# I2C_Multiplexer.net
KiCad netlist of a schematic drawn in Altium Designer
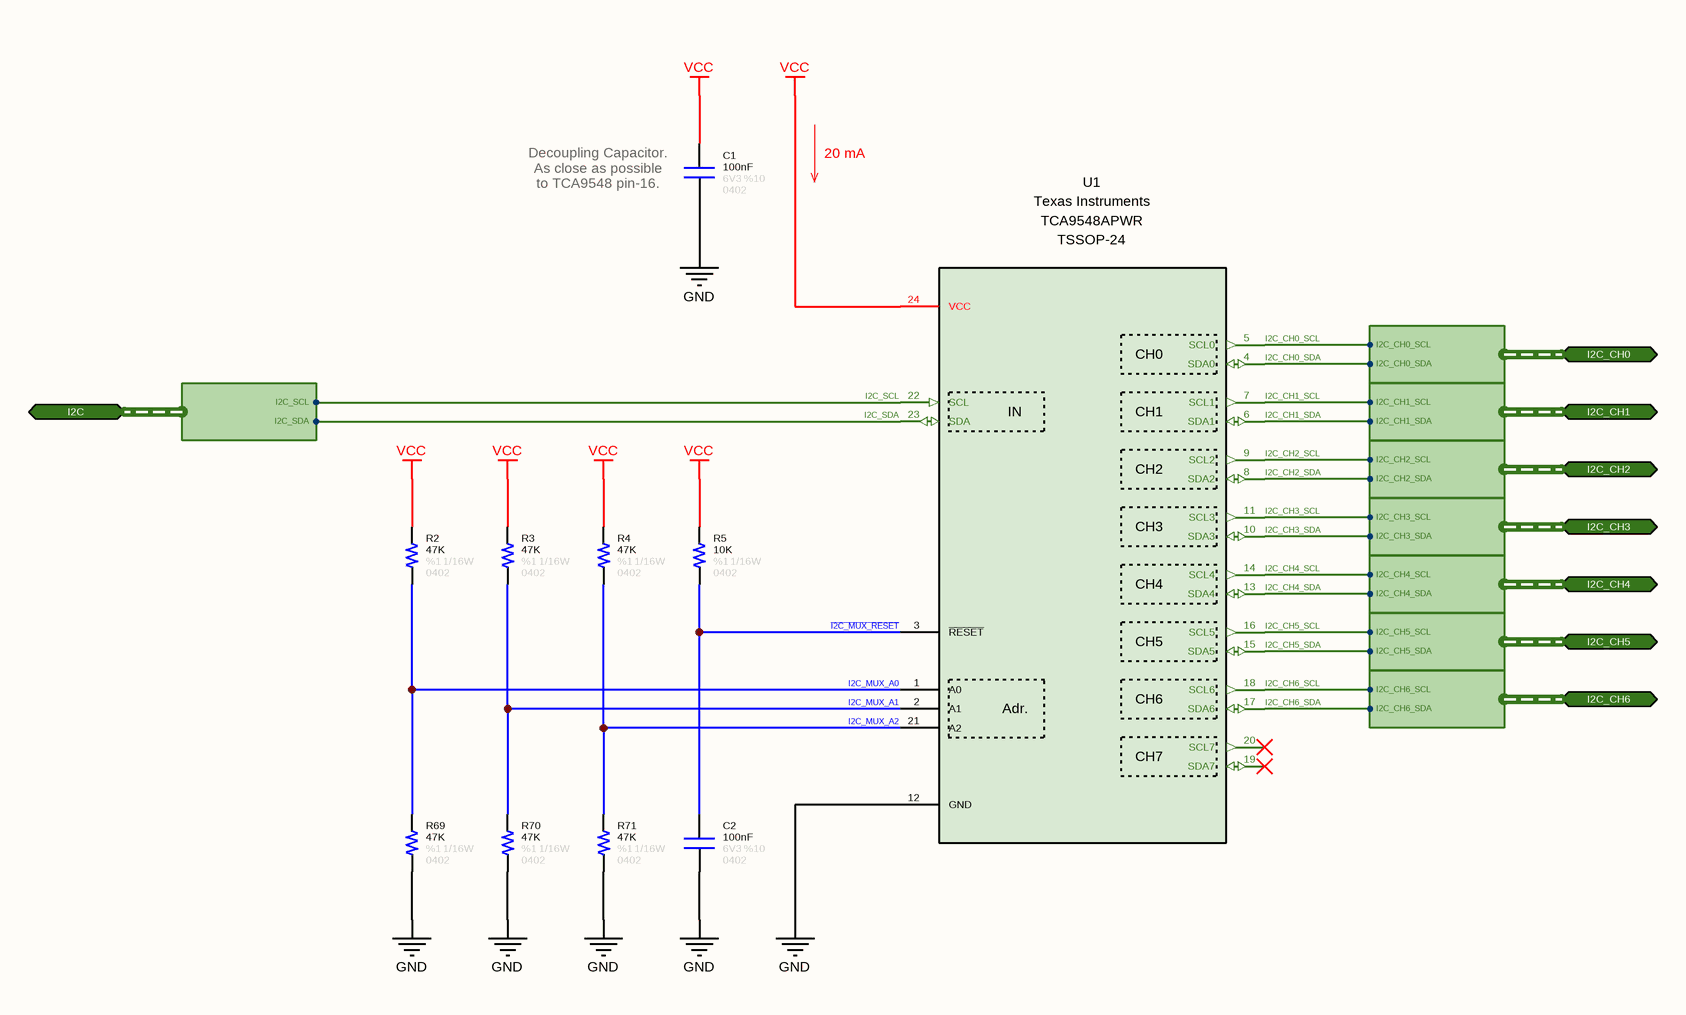
[diagram p0: I2C Multiplexer.SchDoc]

(export (version "E")
  (design (tool "Eeschema 10.0.6"))
  (components
    (comp (ref "C1")
      (value "100nF")
      (footprint "CAPACITOR_0402")
      (description "Capacitor - 100nF [0402-6V3] (Ceramic)")
      (fields
        (field (name "MANUFACTURER PART NUMBER") "04026D104KAT4A")
        (field (name "TOLERANCE") "%10")
        (field (name "VOLTAGE") "6V3")
        (field (name "CASE") "0402")
        (field (name "Comment") "Capacitor - 100nF [0402] (Ceramic)")
      )
      (libsource (lib "P101DA_Library") (part "Capacitor - 100nF [0402-6V3]"))
    )
    (comp (ref "C2")
      (value "100nF")
      (footprint "CAPACITOR_0402")
      (description "Capacitor - 100nF [0402-6V3] (Ceramic)")
      (fields
        (field (name "MANUFACTURER PART NUMBER") "04026D104KAT4A")
        (field (name "TOLERANCE") "%10")
        (field (name "VOLTAGE") "6V3")
        (field (name "CASE") "0402")
        (field (name "Comment") "Capacitor - 100nF [0402] (Ceramic)")
      )
      (libsource (lib "P101DA_Library") (part "Capacitor - 100nF [0402-6V3]"))
    )
    (comp (ref "R2")
      (value "47K")
      (footprint "RESISTOR_0402")
      (description "Thick Film Resistors - SMD 1/16 W 47 KOhm 1%")
      (fields
        (field (name "MANUFACTURER PART NUMBER") "CRCW040247K0FKED")
        (field (name "TOLERANCE") "%1")
        (field (name "CASE") "0402")
        (field (name "POWER") "1/16W")
        (field (name "Comment") "47K - 0402 - %1 - 1/16W")
      )
      (libsource (lib "P101DA_Library") (part "Resistor - 47K [0402]"))
    )
    (comp (ref "R3")
      (value "47K")
      (footprint "RESISTOR_0402")
      (description "Thick Film Resistors - SMD 1/16 W 47 KOhm 1%")
      (fields
        (field (name "MANUFACTURER PART NUMBER") "CRCW040247K0FKED")
        (field (name "TOLERANCE") "%1")
        (field (name "CASE") "0402")
        (field (name "POWER") "1/16W")
        (field (name "Comment") "47K - 0402 - %1 - 1/16W")
      )
      (libsource (lib "P101DA_Library") (part "Resistor - 47K [0402]"))
    )
    (comp (ref "R4")
      (value "47K")
      (footprint "RESISTOR_0402")
      (description "Thick Film Resistors - SMD 1/16 W 47 KOhm 1%")
      (fields
        (field (name "MANUFACTURER PART NUMBER") "CRCW040247K0FKED")
        (field (name "TOLERANCE") "%1")
        (field (name "CASE") "0402")
        (field (name "POWER") "1/16W")
        (field (name "Comment") "47K - 0402 - %1 - 1/16W")
      )
      (libsource (lib "P101DA_Library") (part "Resistor - 47K [0402]"))
    )
    (comp (ref "R5")
      (value "10K")
      (footprint "RESISTOR_0402")
      (description "Thick Film Resistors - SMD 1/16 W 10 KOhm 1%")
      (fields
        (field (name "MANUFACTURER PART NUMBER") "CRCW040210K0FKED")
        (field (name "TOLERANCE") "%1")
        (field (name "CASE") "0402")
        (field (name "POWER") "1/16W")
        (field (name "Comment") "10K - 0402 - %1 - 1/16W")
      )
      (libsource (lib "P101DA_Library") (part "Resistor - 10K [0402]"))
    )
    (comp (ref "R69")
      (value "47K")
      (footprint "RESISTOR_0402")
      (description "Thick Film Resistors - SMD 1/16 W 47 KOhm 1%")
      (fields
        (field (name "MANUFACTURER PART NUMBER") "CRCW040247K0FKED")
        (field (name "TOLERANCE") "%1")
        (field (name "CASE") "0402")
        (field (name "POWER") "1/16W")
        (field (name "Comment") "47K - 0402 - %1 - 1/16W")
      )
      (libsource (lib "P101DA_Library") (part "Resistor - 47K [0402]"))
    )
    (comp (ref "R70")
      (value "47K")
      (footprint "RESISTOR_0402")
      (description "Thick Film Resistors - SMD 1/16 W 47 KOhm 1%")
      (fields
        (field (name "MANUFACTURER PART NUMBER") "CRCW040247K0FKED")
        (field (name "TOLERANCE") "%1")
        (field (name "CASE") "0402")
        (field (name "POWER") "1/16W")
        (field (name "Comment") "47K - 0402 - %1 - 1/16W")
      )
      (libsource (lib "P101DA_Library") (part "Resistor - 47K [0402]"))
    )
    (comp (ref "R71")
      (value "47K")
      (footprint "RESISTOR_0402")
      (description "Thick Film Resistors - SMD 1/16 W 47 KOhm 1%")
      (fields
        (field (name "MANUFACTURER PART NUMBER") "CRCW040247K0FKED")
        (field (name "TOLERANCE") "%1")
        (field (name "CASE") "0402")
        (field (name "POWER") "1/16W")
        (field (name "Comment") "47K - 0402 - %1 - 1/16W")
      )
      (libsource (lib "P101DA_Library") (part "Resistor - 47K [0402]"))
    )
    (comp (ref "U1")
      (value "TCA9548APWR")
      (footprint "TSSOP-24")
      (description "TEXAS INSTRUMENTS - TCA9548APWR - I2C SWITCH W/ RESET, 8-CH, TSSOP-24")
      (fields
        (field (name "MANUFACTURER NAME") "Texas Instruments")
        (field (name "MANUFACTURER PART NUMBER") "TCA9548APWR")
        (field (name "CASE") "TSSOP-24")
      )
      (libsource (lib "P101DA_Library") (part "IC - TCA9548"))
    )
  )
  (nets
    (net (code "9") (name "/I2C_CH0_SCL") (class "Default")
      (node (ref "U1") (pin "5") (pinfunction "SCL0_5") (pintype "output"))
    )
    (net (code "10") (name "/I2C_CH0_SDA") (class "Default")
      (node (ref "U1") (pin "4") (pinfunction "SDA0_4") (pintype "bidirectional"))
    )
    (net (code "11") (name "/I2C_CH1_SCL") (class "Default")
      (node (ref "U1") (pin "7") (pinfunction "SCL1_7") (pintype "output"))
    )
    (net (code "12") (name "/I2C_CH1_SDA") (class "Default")
      (node (ref "U1") (pin "6") (pinfunction "SDA1_6") (pintype "bidirectional"))
    )
    (net (code "13") (name "/I2C_CH2_SCL") (class "Default")
      (node (ref "U1") (pin "9") (pinfunction "SCL2_9") (pintype "output"))
    )
    (net (code "14") (name "/I2C_CH2_SDA") (class "Default")
      (node (ref "U1") (pin "8") (pinfunction "SDA2_8") (pintype "bidirectional"))
    )
    (net (code "15") (name "/I2C_CH3_SCL") (class "Default")
      (node (ref "U1") (pin "11") (pinfunction "SCL3_11") (pintype "output"))
    )
    (net (code "16") (name "/I2C_CH3_SDA") (class "Default")
      (node (ref "U1") (pin "10") (pinfunction "SDA3_10") (pintype "bidirectional"))
    )
    (net (code "17") (name "/I2C_CH4_SCL") (class "Default")
      (node (ref "U1") (pin "14") (pinfunction "SCL4_14") (pintype "output"))
    )
    (net (code "18") (name "/I2C_CH4_SDA") (class "Default")
      (node (ref "U1") (pin "13") (pinfunction "SDA4_13") (pintype "bidirectional"))
    )
    (net (code "19") (name "/I2C_CH5_SCL") (class "Default")
      (node (ref "U1") (pin "16") (pinfunction "SCL5_16") (pintype "output"))
    )
    (net (code "20") (name "/I2C_CH5_SDA") (class "Default")
      (node (ref "U1") (pin "15") (pinfunction "SDA5_15") (pintype "bidirectional"))
    )
    (net (code "21") (name "/I2C_CH6_SCL") (class "Default")
      (node (ref "U1") (pin "18") (pinfunction "SCL6_18") (pintype "output"))
    )
    (net (code "22") (name "/I2C_CH6_SDA") (class "Default")
      (node (ref "U1") (pin "17") (pinfunction "SDA6_17") (pintype "bidirectional"))
    )
    (net (code "23") (name "/I2C_MUX_A0") (class "Default")
      (node (ref "R2") (pin "1") (pinfunction "1_1") (pintype "passive"))
      (node (ref "R69") (pin "2") (pinfunction "2_2") (pintype "passive"))
      (node (ref "U1") (pin "1") (pinfunction "A0_1") (pintype "passive"))
    )
    (net (code "24") (name "/I2C_MUX_A1") (class "Default")
      (node (ref "R3") (pin "1") (pinfunction "1_1") (pintype "passive"))
      (node (ref "R70") (pin "2") (pinfunction "2_2") (pintype "passive"))
      (node (ref "U1") (pin "2") (pinfunction "A1_2") (pintype "passive"))
    )
    (net (code "25") (name "/I2C_MUX_A2") (class "Default")
      (node (ref "R4") (pin "1") (pinfunction "1_1") (pintype "passive"))
      (node (ref "R71") (pin "2") (pinfunction "2_2") (pintype "passive"))
      (node (ref "U1") (pin "21") (pinfunction "A2_21") (pintype "passive"))
    )
    (net (code "26") (name "/I2C_SCL") (class "Default")
      (node (ref "U1") (pin "22") (pinfunction "SCL_22") (pintype "input"))
    )
    (net (code "27") (name "/I2C_SDA") (class "Default")
      (node (ref "U1") (pin "23") (pinfunction "SDA_23") (pintype "bidirectional"))
    )
    (net (code "36") (name "/~{I2C_MUX_RESET}") (class "Default")
      (node (ref "C2") (pin "2") (pinfunction "2_2") (pintype "passive"))
      (node (ref "R5") (pin "1") (pinfunction "1_1") (pintype "passive"))
      (node (ref "U1") (pin "3") (pinfunction "~{RESET}_3") (pintype "power_in"))
    )
    (net (code "37") (name "GND") (class "Default")
      (node (ref "C1") (pin "1") (pinfunction "1_1") (pintype "passive"))
      (node (ref "C2") (pin "1") (pinfunction "1_1") (pintype "passive"))
      (node (ref "R69") (pin "1") (pinfunction "1_1") (pintype "passive"))
      (node (ref "R70") (pin "1") (pinfunction "1_1") (pintype "passive"))
      (node (ref "R71") (pin "1") (pinfunction "1_1") (pintype "passive"))
      (node (ref "U1") (pin "12") (pinfunction "GND_12") (pintype "power_in"))
    )
    (net (code "38") (name "VCC") (class "Default")
      (node (ref "C1") (pin "2") (pinfunction "2_2") (pintype "passive"))
      (node (ref "R2") (pin "2") (pinfunction "2_2") (pintype "passive"))
      (node (ref "R3") (pin "2") (pinfunction "2_2") (pintype "passive"))
      (node (ref "R4") (pin "2") (pinfunction "2_2") (pintype "passive"))
      (node (ref "R5") (pin "2") (pinfunction "2_2") (pintype "passive"))
      (node (ref "U1") (pin "24") (pinfunction "VCC_24") (pintype "power_in"))
    )
    (net (code "39") (name "unconnected-(U1-SCL7-Pad20)") (class "Default")
      (node (ref "U1") (pin "20") (pinfunction "SCL7_20") (pintype "output+no_connect"))
    )
    (net (code "40") (name "unconnected-(U1-SDA7-Pad19)") (class "Default")
      (node (ref "U1") (pin "19") (pinfunction "SDA7_19") (pintype "bidirectional+no_connect"))
    )
  )
)
